# schematic.net
KiCad netlist of a schematic drawn in Altium Designer
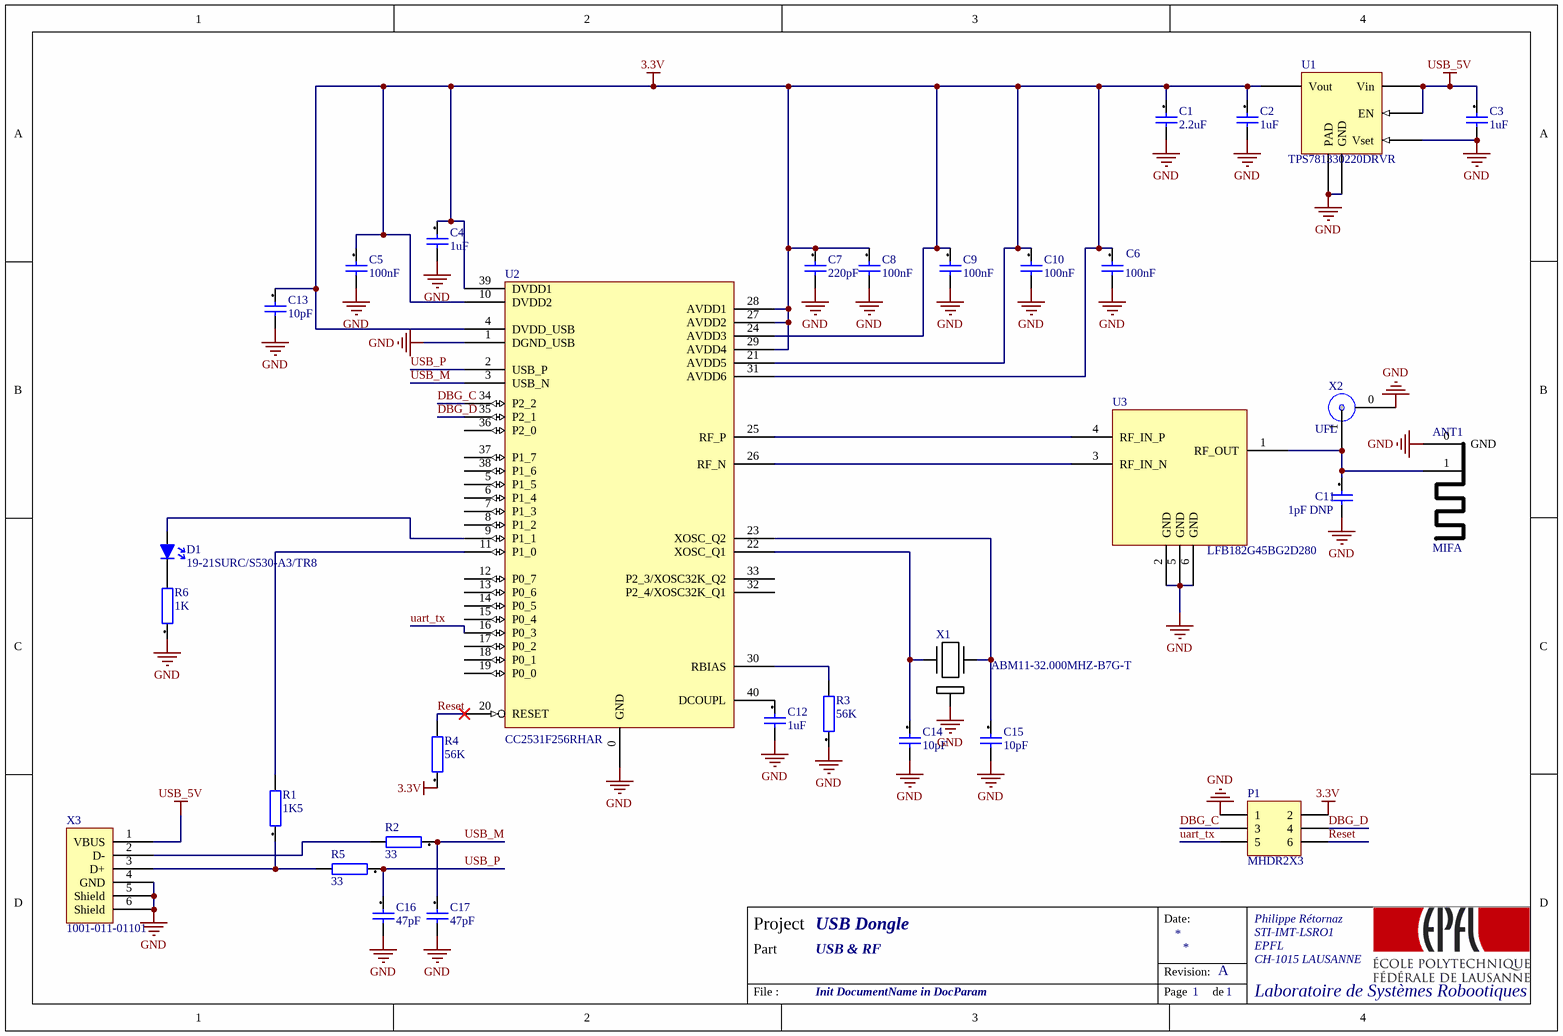
[diagram p0: schematic.SchDoc]

(export (version "E")
  (design (tool "Eeschema 10.0.6"))
  (components
    (comp (ref "ANT1")
      (value "MIFA")
      (footprint "MIFA-2.4GHZ")
      (libsource (lib "cc253x") (part "MIFA_Antenna"))
    )
    (comp (ref "C1")
      (value "2.2uF")
      (footprint "CAPC1005X05L")
      (description "Capacitor")
      (fields (field (name "MANUFACTURER") "Epcos") (field (name "VOLTAGE") "25"))
      (libsource (lib "LSRO1Altium") (part "CAP-NP"))
    )
    (comp (ref "C2")
      (value "1uF")
      (footprint "CAPC1005X05L")
      (description "Capacitor")
      (fields (field (name "MANUFACTURER") "Kemet") (field (name "VOLTAGE") "6.3"))
      (libsource (lib "LSRO1Altium") (part "CAP-NP"))
    )
    (comp (ref "C3")
      (value "1uF")
      (footprint "CAPC1608X08L")
      (description "Capacitor")
      (fields (field (name "MANUFACTURER") "Murata") (field (name "VOLTAGE") "25"))
      (libsource (lib "LSRO1Altium") (part "CAP-NP"))
    )
    (comp (ref "C4")
      (value "1uF")
      (footprint "CAPC1005X05L")
      (description "Capacitor")
      (fields (field (name "MANUFACTURER") "Kemet") (field (name "VOLTAGE") "6.3"))
      (libsource (lib "LSRO1Altium") (part "CAP-NP"))
    )
    (comp (ref "C5")
      (value "100nF")
      (footprint "CAPC1005X05L")
      (description "Capacitor")
      (fields (field (name "MANUFACTURER") "Kemet") (field (name "VOLTAGE") "16"))
      (libsource (lib "LSRO1Altium") (part "CAP-NP"))
    )
    (comp (ref "C6")
      (value "100nF")
      (footprint "CAPC1005X05L")
      (description "Capacitor")
      (fields (field (name "MANUFACTURER") "Kemet") (field (name "VOLTAGE") "16"))
      (libsource (lib "LSRO1Altium") (part "CAP-NP"))
    )
    (comp (ref "C7")
      (value "220pF")
      (footprint "CAPC1005X05L")
      (description "Capacitor")
      (fields (field (name "MANUFACTURER") "Kemet") (field (name "VOLTAGE") "16"))
      (libsource (lib "LSRO1Altium") (part "CAP-NP"))
    )
    (comp (ref "C8")
      (value "100nF")
      (footprint "CAPC1005X05L")
      (description "Capacitor")
      (fields (field (name "MANUFACTURER") "Kemet") (field (name "VOLTAGE") "16"))
      (libsource (lib "LSRO1Altium") (part "CAP-NP"))
    )
    (comp (ref "C9")
      (value "100nF")
      (footprint "CAPC1005X05L")
      (description "Capacitor")
      (fields (field (name "MANUFACTURER") "Kemet") (field (name "VOLTAGE") "16"))
      (libsource (lib "LSRO1Altium") (part "CAP-NP"))
    )
    (comp (ref "C10")
      (value "100nF")
      (footprint "CAPC1005X05L")
      (description "Capacitor")
      (fields (field (name "MANUFACTURER") "Kemet") (field (name "VOLTAGE") "16"))
      (libsource (lib "LSRO1Altium") (part "CAP-NP"))
    )
    (comp (ref "C11")
      (value "1pF DNP")
      (footprint "CAPC1005X05L")
      (description "Capacitor")
      (fields (field (name "MANUFACTURER") "Murata") (field (name "VOLTAGE") "50"))
      (libsource (lib "LSRO1Altium") (part "CAP-NP"))
    )
    (comp (ref "C12")
      (value "1uF")
      (footprint "CAPC1005X05L")
      (description "Capacitor")
      (fields (field (name "MANUFACTURER") "Kemet") (field (name "VOLTAGE") "6.3"))
      (libsource (lib "LSRO1Altium") (part "CAP-NP"))
    )
    (comp (ref "C13")
      (value "10pF")
      (footprint "CAPC1005X05L")
      (description "Capacitor")
      (fields (field (name "MANUFACTURER") "Kemet") (field (name "VOLTAGE") "16"))
      (libsource (lib "LSRO1Altium") (part "CAP-NP"))
    )
    (comp (ref "C14")
      (value "10pF")
      (footprint "CAPC1005X05L")
      (description "Capacitor")
      (fields (field (name "MANUFACTURER") "Murata") (field (name "VOLTAGE") "50"))
      (libsource (lib "LSRO1Altium") (part "CAP-NP"))
    )
    (comp (ref "C15")
      (value "10pF")
      (footprint "CAPC1005X05L")
      (description "Capacitor")
      (fields (field (name "MANUFACTURER") "Murata") (field (name "VOLTAGE") "50"))
      (libsource (lib "LSRO1Altium") (part "CAP-NP"))
    )
    (comp (ref "C16")
      (value "47pF")
      (footprint "CAPC1005X05L")
      (description "Capacitor")
      (fields (field (name "MANUFACTURER") "Murata") (field (name "VOLTAGE") "50"))
      (libsource (lib "LSRO1Altium") (part "CAP-NP"))
    )
    (comp (ref "C17")
      (value "47pF")
      (footprint "CAPC1005X05L")
      (description "Capacitor")
      (fields (field (name "MANUFACTURER") "Murata") (field (name "VOLTAGE") "50"))
      (libsource (lib "LSRO1Altium") (part "CAP-NP"))
    )
    (comp (ref "D1")
      (value "19-21SURC/S530-A3/TR8")
      (footprint "thymio2-main:DIOC1608X08N")
      (description "SMD Red 0603 2V@20ma 56 mcd")
      (fields (field (name "VERIFIEDCOMMENT") "ToDo"))
      (libsource (lib "LEDs") (part "LED"))
    )
    (comp (ref "P1")
      (value "MHDR2X3")
      (footprint "MHDR2X3")
      (description "Header, 3-Pin, Dual row")
      (fields (field (name "PUBLISHER") "Altium Limited"))
      (libsource (lib "Miscellaneous Connectors") (part "MHDR2X3"))
    )
    (comp (ref "R1")
      (value "1K5")
      (footprint "RESC1005X04L")
      (description "Resistor")
      (fields (field (name "TOLERANCE") "+/-1") (field (name "MANUFACTURER") "Phycomp"))
      (libsource (lib "LSRO1Altium") (part "RES"))
    )
    (comp (ref "R2")
      (value "33")
      (footprint "RESC1005X04L")
      (description "Resistor")
      (fields (field (name "TOLERANCE") "+/-1") (field (name "MANUFACTURER") "Phycomp"))
      (libsource (lib "LSRO1Altium") (part "RES"))
    )
    (comp (ref "R3")
      (value "56K")
      (footprint "RESC1005X04L")
      (description "Resistor")
      (fields (field (name "TOLERANCE") "+/-1") (field (name "MANUFACTURER") "Phycomp"))
      (libsource (lib "LSRO1Altium") (part "RES"))
    )
    (comp (ref "R4")
      (value "56K")
      (footprint "RESC1005X04L")
      (description "Resistor")
      (fields (field (name "TOLERANCE") "+/-1") (field (name "MANUFACTURER") "Phycomp"))
      (libsource (lib "LSRO1Altium") (part "RES"))
    )
    (comp (ref "R5")
      (value "33")
      (footprint "RESC1005X04L")
      (description "Resistor")
      (fields (field (name "TOLERANCE") "+/-1") (field (name "MANUFACTURER") "Phycomp"))
      (libsource (lib "LSRO1Altium") (part "RES"))
    )
    (comp (ref "R6")
      (value "1K")
      (footprint "RESC1005X04L")
      (description "Resistor")
      (fields (field (name "TOLERANCE") "+/-1") (field (name "MANUFACTURER") "Phycomp"))
      (libsource (lib "LSRO1Altium") (part "RES"))
    )
    (comp (ref "U1")
      (value "TPS781330220DRVR")
      (footprint "QFN65P200X200X80-6N")
      (description "150mA LDO")
      (libsource (lib "cc253x") (part "TPS781"))
    )
    (comp (ref "U2")
      (value "CC2531F256RHAR")
      (footprint "module:QFN50P600X600X100-40L-2")
      (description "System-on-Chip Solution for IEEE 802.15.4")
      (libsource (lib "cc253x") (part "cc2531"))
    )
    (comp (ref "U3")
      (value "LFB182G45BG2D280")
      (footprint "LFB182G45BG2D280")
      (description "Balun for CC253x")
      (libsource (lib "cc253x") (part "2450BM15A0002"))
    )
    (comp (ref "X1")
      (value "ABM11-32.000MHZ-B7G-T")
      (footprint "Abracon-ABM11")
      (description "32Mhz Crystal, 15ppm")
      (libsource (lib "cc253x") (part "ABM11-32.000MHZ-B7G-T"))
    )
    (comp (ref "X2")
      (value "UFL")
      (footprint "U.FL-R-SMT-1")
      (libsource (lib "cc253x") (part "U.FL-R-SMT-1"))
    )
    (comp (ref "X3")
      (value "1001-011-01101")
      (footprint "1001-011-01101")
      (description "USB CONNECTOR, A TYPE")
      (libsource (lib "cc253x") (part "USB-A-Device"))
    )
  )
  (nets
    (net (code "1") (name "/DBG_C") (class "Default")
      (node (ref "P1") (pin "3") (pinfunction "3_3") (pintype "passive"))
      (node (ref "U2") (pin "34") (pinfunction "P2_2_34") (pintype "bidirectional"))
    )
    (net (code "2") (name "/DBG_D") (class "Default")
      (node (ref "P1") (pin "4") (pinfunction "4_4") (pintype "passive"))
      (node (ref "U2") (pin "35") (pinfunction "P2_1_35") (pintype "bidirectional"))
    )
    (net (code "3") (name "/Reset") (class "Default")
      (node (ref "P1") (pin "6") (pinfunction "6_6") (pintype "passive"))
      (node (ref "R4") (pin "2") (pinfunction "2_2") (pintype "passive"))
      (node (ref "U2") (pin "20") (pinfunction "RESET_20") (pintype "input"))
    )
    (net (code "4") (name "/USB_M") (class "Default")
      (node (ref "C17") (pin "1") (pinfunction "1_1") (pintype "passive"))
      (node (ref "R2") (pin "1") (pinfunction "1_1") (pintype "passive"))
      (node (ref "U2") (pin "3") (pinfunction "USB_N_3") (pintype "passive"))
    )
    (net (code "5") (name "/USB_P") (class "Default")
      (node (ref "C16") (pin "1") (pinfunction "1_1") (pintype "passive"))
      (node (ref "R5") (pin "1") (pinfunction "1_1") (pintype "passive"))
      (node (ref "U2") (pin "2") (pinfunction "USB_P_2") (pintype "passive"))
    )
    (net (code "6") (name "/uart_tx") (class "Default")
      (node (ref "P1") (pin "5") (pinfunction "5_5") (pintype "passive"))
      (node (ref "U2") (pin "16") (pinfunction "P0_3_16") (pintype "bidirectional"))
    )
    (net (code "7") (name "3.3V") (class "Default")
      (node (ref "C1") (pin "1") (pinfunction "1_1") (pintype "passive"))
      (node (ref "C10") (pin "1") (pinfunction "1_1") (pintype "passive"))
      (node (ref "C13") (pin "1") (pinfunction "1_1") (pintype "passive"))
      (node (ref "C2") (pin "1") (pinfunction "1_1") (pintype "passive"))
      (node (ref "C4") (pin "1") (pinfunction "1_1") (pintype "passive"))
      (node (ref "C5") (pin "1") (pinfunction "1_1") (pintype "passive"))
      (node (ref "C6") (pin "1") (pinfunction "1_1") (pintype "passive"))
      (node (ref "C7") (pin "1") (pinfunction "1_1") (pintype "passive"))
      (node (ref "C8") (pin "1") (pinfunction "1_1") (pintype "passive"))
      (node (ref "C9") (pin "1") (pinfunction "1_1") (pintype "passive"))
      (node (ref "P1") (pin "2") (pinfunction "2_2") (pintype "passive"))
      (node (ref "R4") (pin "1") (pinfunction "1_1") (pintype "passive"))
      (node (ref "U1") (pin "5") (pinfunction "Vout_5") (pintype "power_in"))
      (node (ref "U2") (pin "10") (pinfunction "DVDD2_10") (pintype "power_in"))
      (node (ref "U2") (pin "21") (pinfunction "AVDD5_21") (pintype "power_in"))
      (node (ref "U2") (pin "24") (pinfunction "AVDD3_24") (pintype "power_in"))
      (node (ref "U2") (pin "27") (pinfunction "AVDD2_27") (pintype "power_in"))
      (node (ref "U2") (pin "28") (pinfunction "AVDD1_28") (pintype "power_in"))
      (node (ref "U2") (pin "29") (pinfunction "AVDD4_29") (pintype "power_in"))
      (node (ref "U2") (pin "31") (pinfunction "AVDD6_31") (pintype "power_in"))
      (node (ref "U2") (pin "39") (pinfunction "DVDD1_39") (pintype "power_in"))
      (node (ref "U2") (pin "4") (pinfunction "DVDD_USB_4") (pintype "power_in"))
    )
    (net (code "8") (name "GND") (class "Default")
      (node (ref "ANT1") (pin "0") (pinfunction "GND_0") (pintype "passive"))
      (node (ref "C1") (pin "2") (pinfunction "2_2") (pintype "passive"))
      (node (ref "C10") (pin "2") (pinfunction "2_2") (pintype "passive"))
      (node (ref "C11") (pin "2") (pinfunction "2_2") (pintype "passive"))
      (node (ref "C12") (pin "2") (pinfunction "2_2") (pintype "passive"))
      (node (ref "C13") (pin "2") (pinfunction "2_2") (pintype "passive"))
      (node (ref "C14") (pin "2") (pinfunction "2_2") (pintype "passive"))
      (node (ref "C15") (pin "2") (pinfunction "2_2") (pintype "passive"))
      (node (ref "C16") (pin "2") (pinfunction "2_2") (pintype "passive"))
      (node (ref "C17") (pin "2") (pinfunction "2_2") (pintype "passive"))
      (node (ref "C2") (pin "2") (pinfunction "2_2") (pintype "passive"))
      (node (ref "C3") (pin "2") (pinfunction "2_2") (pintype "passive"))
      (node (ref "C4") (pin "2") (pinfunction "2_2") (pintype "passive"))
      (node (ref "C5") (pin "2") (pinfunction "2_2") (pintype "passive"))
      (node (ref "C6") (pin "2") (pinfunction "2_2") (pintype "passive"))
      (node (ref "C7") (pin "2") (pinfunction "2_2") (pintype "passive"))
      (node (ref "C8") (pin "2") (pinfunction "2_2") (pintype "passive"))
      (node (ref "C9") (pin "2") (pinfunction "2_2") (pintype "passive"))
      (node (ref "P1") (pin "1") (pinfunction "1_1") (pintype "passive"))
      (node (ref "R3") (pin "1") (pinfunction "1_1") (pintype "passive"))
      (node (ref "R6") (pin "1") (pinfunction "1_1") (pintype "passive"))
      (node (ref "U1") (pin "3") (pinfunction "Vset_3") (pintype "input"))
      (node (ref "U1") (pin "4") (pinfunction "GND_4") (pintype "power_in"))
      (node (ref "U1") (pin "7") (pinfunction "PAD_7") (pintype "passive"))
      (node (ref "U2") (pin "0") (pinfunction "GND_0") (pintype "power_in"))
      (node (ref "U2") (pin "1") (pinfunction "DGND_USB_1") (pintype "power_in"))
      (node (ref "U3") (pin "2") (pinfunction "GND_2") (pintype "passive"))
      (node (ref "U3") (pin "5") (pinfunction "GND_5") (pintype "passive"))
      (node (ref "U3") (pin "6") (pinfunction "GND_6") (pintype "passive"))
      (node (ref "X1") (pin "0") (pinfunction "GND_0") (pintype "power_in"))
      (node (ref "X2") (pin "0") (pinfunction "NC_0") (pintype "power_in"))
      (node (ref "X3") (pin "4") (pinfunction "GND_4") (pintype "passive"))
      (node (ref "X3") (pin "5") (pinfunction "Shield_5") (pintype "passive"))
      (node (ref "X3") (pin "6") (pinfunction "Shield_6") (pintype "passive"))
    )
    (net (code "9") (name "Net-(D1-A)") (class "Default")
      (node (ref "D1") (pin "2") (pinfunction "A_2") (pintype "passive"))
      (node (ref "U2") (pin "9") (pinfunction "P1_1_9") (pintype "bidirectional"))
    )
    (net (code "10") (name "Net-(D1-K)") (class "Default")
      (node (ref "D1") (pin "1") (pinfunction "K_1") (pintype "passive"))
      (node (ref "R6") (pin "2") (pinfunction "2_2") (pintype "passive"))
    )
    (net (code "11") (name "Net-(U2-DCOUPL)") (class "Default")
      (node (ref "C12") (pin "1") (pinfunction "1_1") (pintype "passive"))
      (node (ref "U2") (pin "40") (pinfunction "DCOUPL_40") (pintype "passive"))
    )
    (net (code "12") (name "Net-(U2-P1_0)") (class "Default")
      (node (ref "R1") (pin "2") (pinfunction "2_2") (pintype "passive"))
      (node (ref "U2") (pin "11") (pinfunction "P1_0_11") (pintype "bidirectional"))
    )
    (net (code "13") (name "Net-(U2-RBIAS)") (class "Default")
      (node (ref "R3") (pin "2") (pinfunction "2_2") (pintype "passive"))
      (node (ref "U2") (pin "30") (pinfunction "RBIAS_30") (pintype "passive"))
    )
    (net (code "14") (name "Net-(U2-RF_N)") (class "Default")
      (node (ref "U2") (pin "26") (pinfunction "RF_N_26") (pintype "passive"))
      (node (ref "U3") (pin "3") (pinfunction "RF_IN_N_3") (pintype "passive"))
    )
    (net (code "15") (name "Net-(U2-RF_P)") (class "Default")
      (node (ref "U2") (pin "25") (pinfunction "RF_P_25") (pintype "passive"))
      (node (ref "U3") (pin "4") (pinfunction "RF_IN_P_4") (pintype "passive"))
    )
    (net (code "16") (name "Net-(U2-XOSC_Q1)") (class "Default")
      (node (ref "C14") (pin "1") (pinfunction "1_1") (pintype "passive"))
      (node (ref "U2") (pin "22") (pinfunction "XOSC_Q1_22") (pintype "passive"))
      (node (ref "X1") (pin "1") (pinfunction "1_1") (pintype "power_in"))
    )
    (net (code "17") (name "Net-(U2-XOSC_Q2)") (class "Default")
      (node (ref "C15") (pin "1") (pinfunction "1_1") (pintype "passive"))
      (node (ref "U2") (pin "23") (pinfunction "XOSC_Q2_23") (pintype "passive"))
      (node (ref "X1") (pin "2") (pinfunction "2_2") (pintype "power_in"))
    )
    (net (code "18") (name "Net-(U3-RF_OUT)") (class "Default")
      (node (ref "ANT1") (pin "1") (pintype "passive"))
      (node (ref "C11") (pin "1") (pinfunction "1_1") (pintype "passive"))
      (node (ref "U3") (pin "1") (pinfunction "RF_OUT_1") (pintype "passive"))
      (node (ref "X2") (pin "1") (pinfunction "1_1") (pintype "passive"))
    )
    (net (code "19") (name "Net-(X3-D+)") (class "Default")
      (node (ref "R1") (pin "1") (pinfunction "1_1") (pintype "passive"))
      (node (ref "R5") (pin "2") (pinfunction "2_2") (pintype "passive"))
      (node (ref "X3") (pin "3") (pinfunction "D+_3") (pintype "passive"))
    )
    (net (code "20") (name "Net-(X3-D-)") (class "Default")
      (node (ref "R2") (pin "2") (pinfunction "2_2") (pintype "passive"))
      (node (ref "X3") (pin "2") (pinfunction "D-_2") (pintype "passive"))
    )
    (net (code "21") (name "USB_5V") (class "Default")
      (node (ref "C3") (pin "1") (pinfunction "1_1") (pintype "passive"))
      (node (ref "U1") (pin "1") (pinfunction "Vin_1") (pintype "power_in"))
      (node (ref "U1") (pin "2") (pinfunction "EN_2") (pintype "input"))
      (node (ref "X3") (pin "1") (pinfunction "VBUS_1") (pintype "passive"))
    )
    (net (code "22") (name "unconnected-(U2-P0_0-Pad19)") (class "Default")
      (node (ref "U2") (pin "19") (pinfunction "P0_0_19") (pintype "bidirectional"))
    )
    (net (code "23") (name "unconnected-(U2-P0_1-Pad18)") (class "Default")
      (node (ref "U2") (pin "18") (pinfunction "P0_1_18") (pintype "bidirectional"))
    )
    (net (code "24") (name "unconnected-(U2-P0_2-Pad17)") (class "Default")
      (node (ref "U2") (pin "17") (pinfunction "P0_2_17") (pintype "bidirectional"))
    )
    (net (code "25") (name "unconnected-(U2-P0_4-Pad15)") (class "Default")
      (node (ref "U2") (pin "15") (pinfunction "P0_4_15") (pintype "bidirectional"))
    )
    (net (code "26") (name "unconnected-(U2-P0_5-Pad14)") (class "Default")
      (node (ref "U2") (pin "14") (pinfunction "P0_5_14") (pintype "bidirectional"))
    )
    (net (code "27") (name "unconnected-(U2-P0_6-Pad13)") (class "Default")
      (node (ref "U2") (pin "13") (pinfunction "P0_6_13") (pintype "bidirectional"))
    )
    (net (code "28") (name "unconnected-(U2-P0_7-Pad12)") (class "Default")
      (node (ref "U2") (pin "12") (pinfunction "P0_7_12") (pintype "bidirectional"))
    )
    (net (code "29") (name "unconnected-(U2-P1_2-Pad8)") (class "Default")
      (node (ref "U2") (pin "8") (pinfunction "P1_2_8") (pintype "bidirectional"))
    )
    (net (code "30") (name "unconnected-(U2-P1_3-Pad7)") (class "Default")
      (node (ref "U2") (pin "7") (pinfunction "P1_3_7") (pintype "bidirectional"))
    )
    (net (code "31") (name "unconnected-(U2-P1_4-Pad6)") (class "Default")
      (node (ref "U2") (pin "6") (pinfunction "P1_4_6") (pintype "bidirectional"))
    )
    (net (code "32") (name "unconnected-(U2-P1_5-Pad5)") (class "Default")
      (node (ref "U2") (pin "5") (pinfunction "P1_5_5") (pintype "bidirectional"))
    )
    (net (code "33") (name "unconnected-(U2-P1_6-Pad38)") (class "Default")
      (node (ref "U2") (pin "38") (pinfunction "P1_6_38") (pintype "bidirectional"))
    )
    (net (code "34") (name "unconnected-(U2-P1_7-Pad37)") (class "Default")
      (node (ref "U2") (pin "37") (pinfunction "P1_7_37") (pintype "bidirectional"))
    )
    (net (code "35") (name "unconnected-(U2-P2_0-Pad36)") (class "Default")
      (node (ref "U2") (pin "36") (pinfunction "P2_0_36") (pintype "bidirectional"))
    )
    (net (code "36") (name "unconnected-(U2-P2_3{slash}XOSC32K_Q2-Pad33)") (class "Default")
      (node (ref "U2") (pin "33") (pinfunction "P2_3/XOSC32K_Q2_33") (pintype "passive"))
    )
    (net (code "37") (name "unconnected-(U2-P2_4{slash}XOSC32K_Q1-Pad32)") (class "Default")
      (node (ref "U2") (pin "32") (pinfunction "P2_4/XOSC32K_Q1_32") (pintype "passive"))
    )
  )
)
